# ProPrj_EDA-Piano2_2025-09-29.net
KiCad netlist of a schematic drawn in EasyEDA Pro
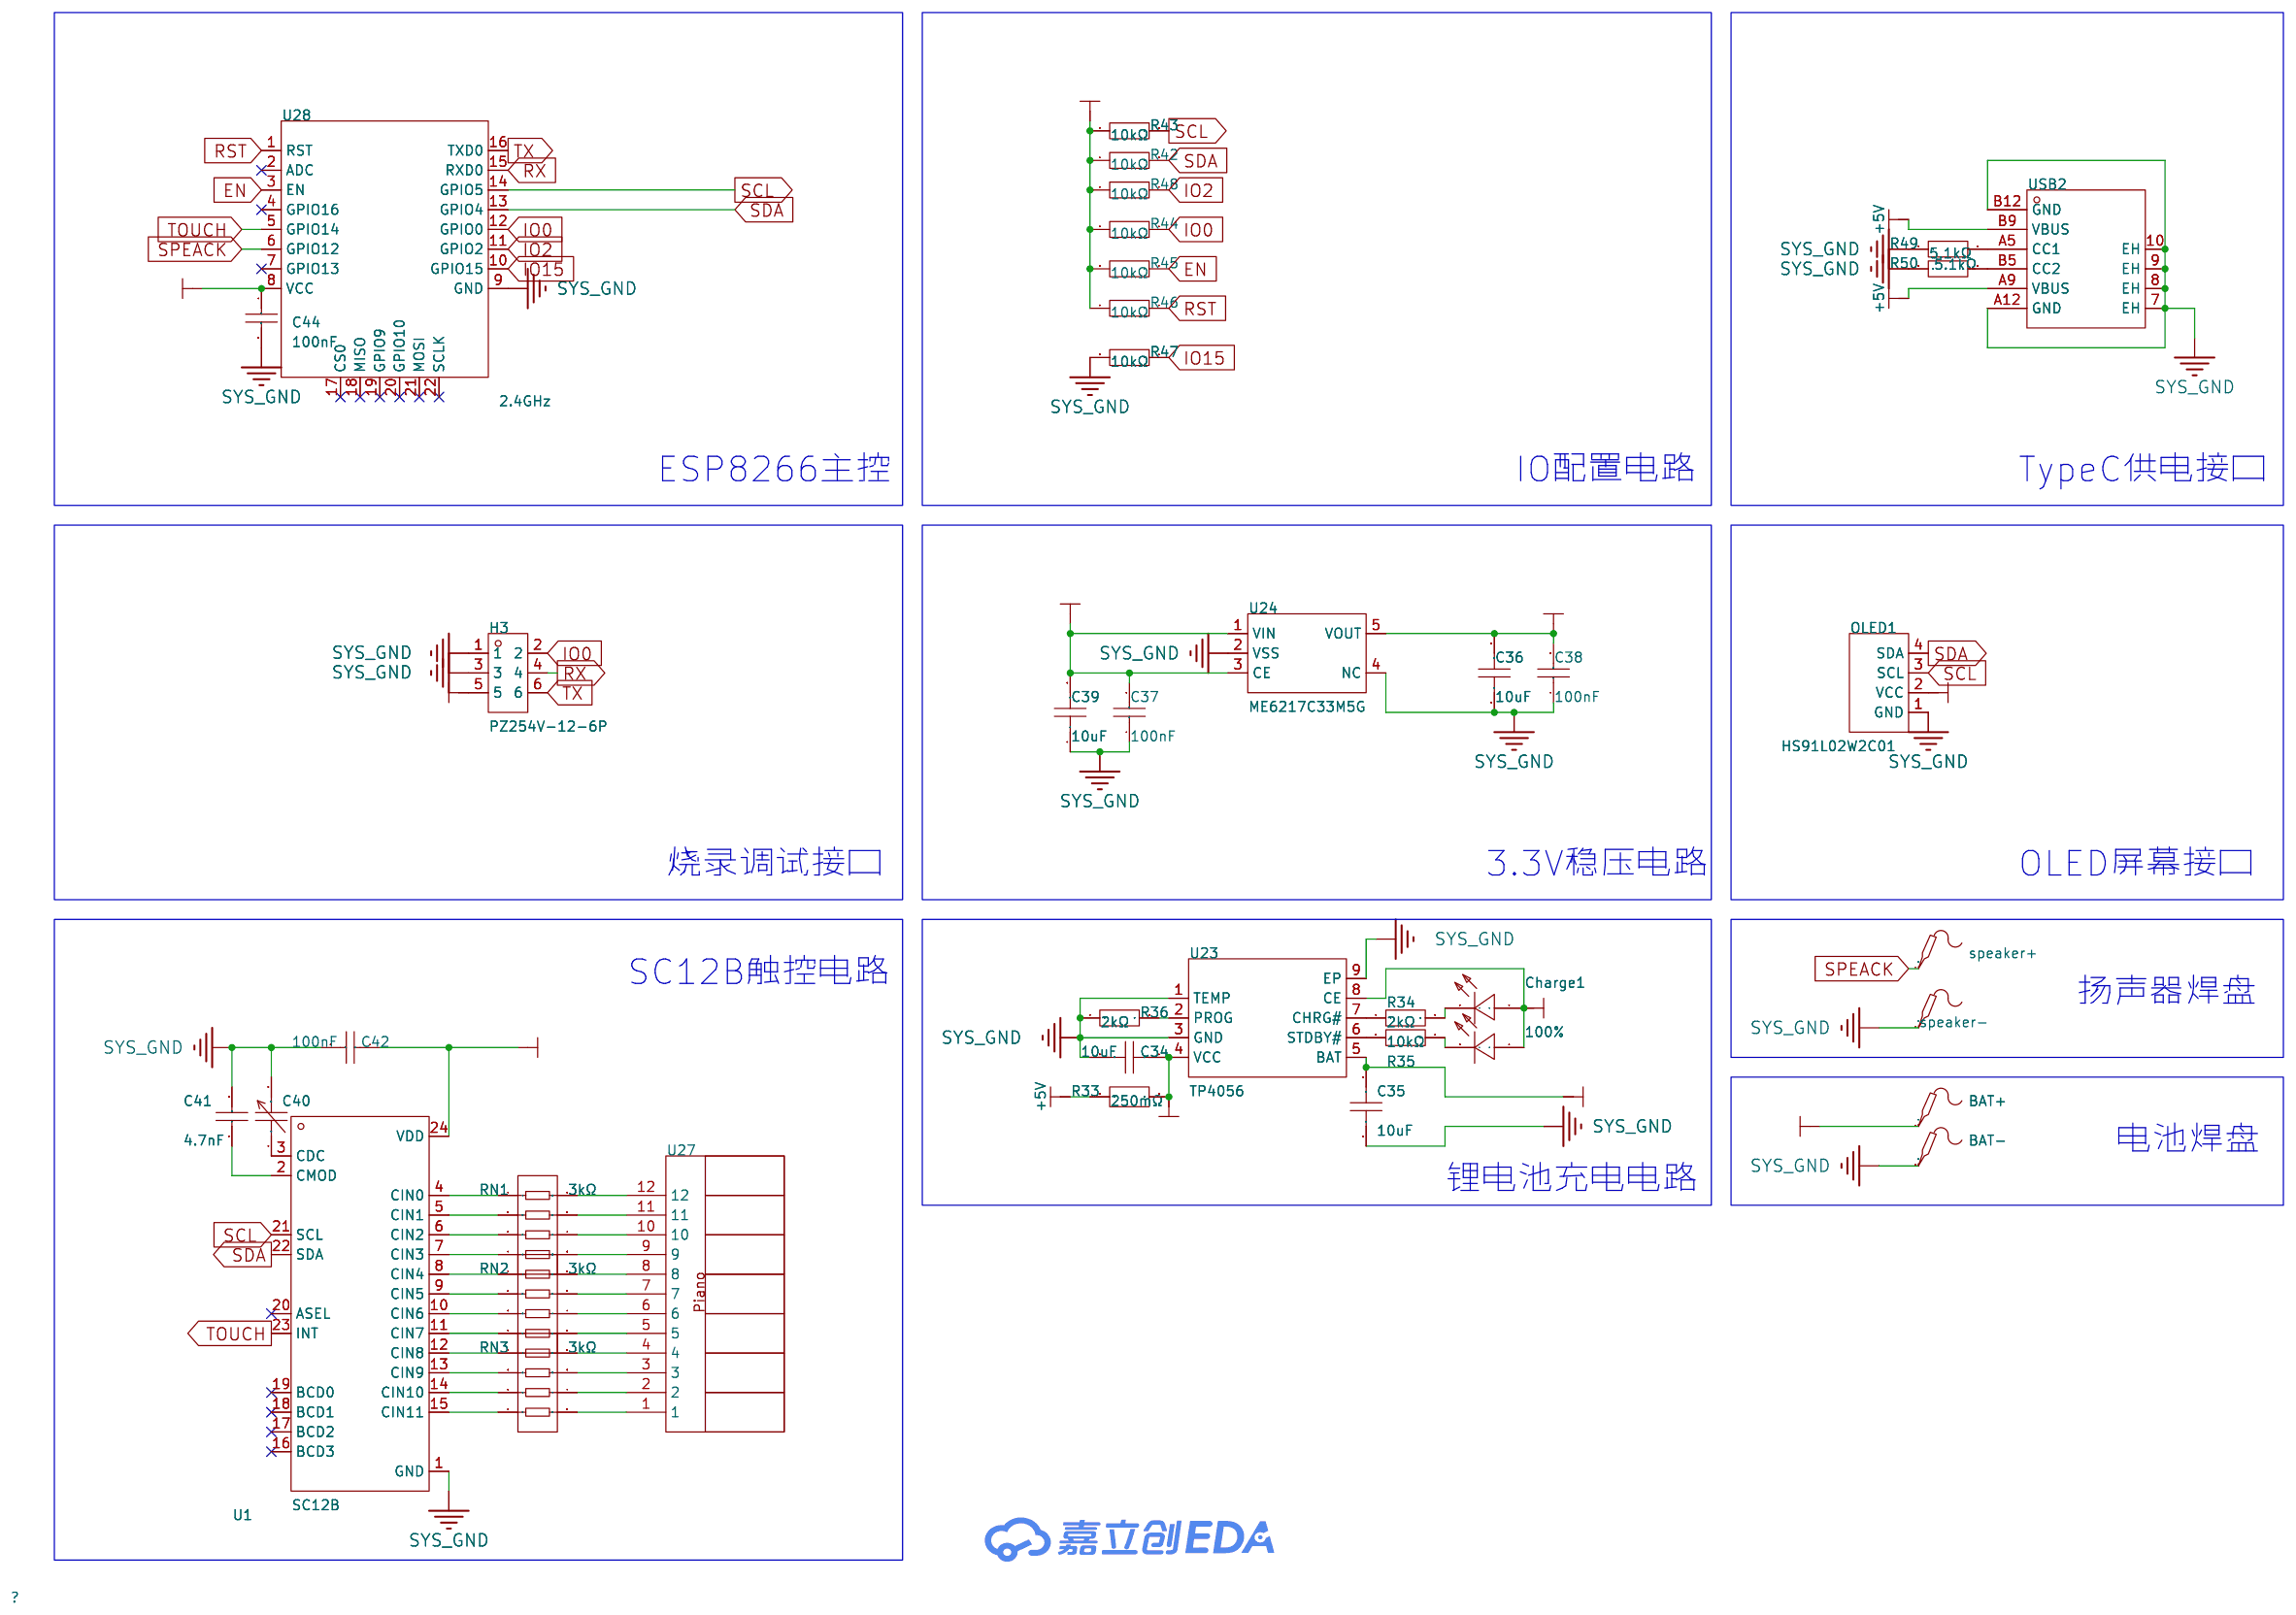
[diagram p0: schematic sheet]

(export (version "E")
  (design (tool "Eeschema 10.0.6"))
  (components
    (comp (ref "100%")
      (value "NCD0805R1")
      (footprint "easyedapro:LED0805-R-RD")
      (fields (field (name "Manufacturer") "国星光电"))
      (libsource (lib "easyedapro") (part "FC-2012HRK-620D"))
    )
    (comp (ref "BAT+")
      (value "~")
      (footprint "easyedapro:Test-Point-0.5mm")
      (description "Test Point 测试点")
      (libsource (lib "easyedapro") (part "Test-Point"))
    )
    (comp (ref "BAT-")
      (value "~")
      (footprint "easyedapro:Test-Point-0.5mm")
      (description "Test Point 测试点")
      (libsource (lib "easyedapro") (part "Test-Point"))
    )
    (comp (ref "C34")
      (value "10uF")
      (fields
        (field (name "Manufacturer Part") "CGA0805X5R106K250MT")
        (field (name "Manufacturer") "HRE(芯声)")
      )
      (libsource (lib "easyedapro") (part "CL10A106MA8NRNC"))
    )
    (comp (ref "C35")
      (value "10uF")
      (fields
        (field (name "Manufacturer Part") "CGA0805X5R106K250MT")
        (field (name "Manufacturer") "HRE(芯声)")
      )
      (libsource (lib "easyedapro") (part "CL10A106MA8NRNC"))
    )
    (comp (ref "C36")
      (value "10uF")
      (footprint "easyedapro:C0805")
      (description "容值:10uF;精度:±10%;额定电压:25V;材质(温度系数):X5R;")
      (fields
        (field (name "Manufacturer Part") "CL21A106KAYNNNE")
        (field (name "Manufacturer") "SAMSUNG(三星)")
      )
      (libsource (lib "easyedapro") (part "CL21A106KAYNNNE"))
    )
    (comp (ref "C37")
      (value "100nF")
      (fields
        (field (name "Manufacturer Part") "FCC0805B104K500DT")
        (field (name "Manufacturer") "FOJAN(富捷)")
      )
      (libsource (lib "easyedapro") (part "CL21A475KAQNNNE"))
    )
    (comp (ref "C38")
      (value "100nF")
      (fields
        (field (name "Manufacturer Part") "FCC0805B104K500DT")
        (field (name "Manufacturer") "FOJAN(富捷)")
      )
      (libsource (lib "easyedapro") (part "CL21A475KAQNNNE"))
    )
    (comp (ref "C39")
      (value "10uF")
      (footprint "easyedapro:C0805")
      (description "容值:10uF;精度:±10%;额定电压:25V;材质(温度系数):X5R;")
      (fields
        (field (name "Manufacturer Part") "CL21A106KAYNNNE")
        (field (name "Manufacturer") "SAMSUNG(三星)")
      )
      (libsource (lib "easyedapro") (part "CL21A106KAYNNNE"))
    )
    (comp (ref "C40")
      (value "STC3ME30-T1")
      (footprint "easyedapro:CAP-SMD_L4.5-W3.2_SGC3S200NM")
      (description "静电容量:8pF~28.5pF;静电容量公差:0%~+50%;额定电压(Vdc):100V;Q值:250@1MHz;")
      (fields (field (name "Manufacturer") "SEHWA(韩国世华)"))
      (libsource (lib "easyedapro") (part "STC3ME30-T1_C22468123"))
    )
    (comp (ref "C41")
      (value "4.7nF")
      (footprint "easyedapro:C0805")
      (description "容值:4.7nF;精度:±10%;额定电压:50V;温度系数:X7R;")
      (fields (field (name "Manufacturer Part") "0805B472K500NT") (field (name "Manufacturer") "FH(风华)"))
      (libsource (lib "easyedapro") (part "0805B472K500NT"))
    )
    (comp (ref "C42")
      (value "100nF")
      (fields
        (field (name "Manufacturer Part") "FCC0805B104K500DT")
        (field (name "Manufacturer") "FOJAN(富捷)")
      )
      (libsource (lib "easyedapro") (part "CL21A475KAQNNNE"))
    )
    (comp (ref "C44")
      (value "100nF")
      (fields
        (field (name "Manufacturer Part") "FCC0805B104K500DT")
        (field (name "Manufacturer") "FOJAN(富捷)")
      )
      (libsource (lib "easyedapro") (part "CL21A475KAQNNNE"))
    )
    (comp (ref "Charge1")
      (value "NCD0805R1")
      (footprint "easyedapro:LED0805-R-RD")
      (fields (field (name "Manufacturer") "国星光电"))
      (libsource (lib "easyedapro") (part "FC-2012HRK-620D"))
    )
    (comp (ref "H3")
      (value "PZ254V-12-6P")
      (footprint "easyedapro:HDR-TH_6P-P2.54-V-M-R2-C3-S2.54")
      (fields (field (name "Manufacturer") "XFCN(兴飞)"))
      (libsource (lib "easyedapro") (part "PZ254V-12-6P"))
    )
    (comp (ref "OLED1")
      (value "HS91L02W2C01")
      (footprint "easyedapro:OLED-TH_L38.0-W12.0_HS91L02W2C01")
      (description "主控芯片:SSD1306;接口类型:I2C;尺寸(inch):0.91;像素分辨率:128x32;")
      (fields (field (name "Manufacturer") "HS(汉昇)"))
      (libsource (lib "easyedapro") (part "HS91L02W2C01"))
    )
    (comp (ref "R33")
      (value "250mΩ")
      (footprint "easyedapro:R0805")
      (description "电阻类型:厚膜电阻;阻值:250mΩ;精度:±5%;功率:125mW;最大工作电压:300V;温度系数:±300ppm/°C;")
      (fields (field (name "Manufacturer Part") "FRL0805JR250TS") (field (name "Manufacturer") "FOJAN(富捷)"))
      (libsource (lib "easyedapro") (part "FRL0805JR250TS"))
    )
    (comp (ref "R34")
      (value "2kΩ")
      (footprint "easyedapro:R0805")
      (description "电阻类型:厚膜电阻;阻值:2kΩ;精度:±1%;功率:125mW;最大工作电压:150V;温度系数:±100ppm/°C;")
      (fields
        (field (name "Manufacturer Part") "0805W8F2001T5E")
        (field (name "Manufacturer") "UNI-ROYAL(厚声)")
      )
      (libsource (lib "easyedapro") (part "0805W8F2001T5E"))
    )
    (comp (ref "R35")
      (value "10kΩ")
      (footprint "easyedapro:R0805")
      (description "电阻类型:厚膜电阻;阻值:10kΩ;精度:±1%;功率:125mW;最大工作电压:150V;温度系数:±100ppm/°C;")
      (fields
        (field (name "Manufacturer Part") "0805W8F1002T5E")
        (field (name "Manufacturer") "UNI-ROYAL(厚声)")
      )
      (libsource (lib "easyedapro") (part "0805W8F1002T5E"))
    )
    (comp (ref "R36")
      (value "2kΩ")
      (footprint "easyedapro:R0805")
      (description "电阻类型:厚膜电阻;阻值:2kΩ;精度:±1%;功率:125mW;最大工作电压:150V;温度系数:±100ppm/°C;")
      (fields
        (field (name "Manufacturer Part") "0805W8F2001T5E")
        (field (name "Manufacturer") "UNI-ROYAL(厚声)")
      )
      (libsource (lib "easyedapro") (part "0805W8F2001T5E"))
    )
    (comp (ref "R42")
      (value "10kΩ")
      (footprint "easyedapro:R0805")
      (description "电阻类型:厚膜电阻;阻值:10kΩ;精度:±1%;功率:125mW;最大工作电压:150V;温度系数:±100ppm/°C;")
      (fields
        (field (name "Manufacturer Part") "0805W8F1002T5E")
        (field (name "Manufacturer") "UNI-ROYAL(厚声)")
      )
      (libsource (lib "easyedapro") (part "0805W8F1002T5E"))
    )
    (comp (ref "R43")
      (value "10kΩ")
      (footprint "easyedapro:R0805")
      (description "电阻类型:厚膜电阻;阻值:10kΩ;精度:±1%;功率:125mW;最大工作电压:150V;温度系数:±100ppm/°C;")
      (fields
        (field (name "Manufacturer Part") "0805W8F1002T5E")
        (field (name "Manufacturer") "UNI-ROYAL(厚声)")
      )
      (libsource (lib "easyedapro") (part "0805W8F1002T5E"))
    )
    (comp (ref "R44")
      (value "10kΩ")
      (footprint "easyedapro:R0805")
      (description "电阻类型:厚膜电阻;阻值:10kΩ;精度:±1%;功率:125mW;最大工作电压:150V;温度系数:±100ppm/°C;")
      (fields
        (field (name "Manufacturer Part") "0805W8F1002T5E")
        (field (name "Manufacturer") "UNI-ROYAL(厚声)")
      )
      (libsource (lib "easyedapro") (part "0805W8F1002T5E"))
    )
    (comp (ref "R45")
      (value "10kΩ")
      (footprint "easyedapro:R0805")
      (description "电阻类型:厚膜电阻;阻值:10kΩ;精度:±1%;功率:125mW;最大工作电压:150V;温度系数:±100ppm/°C;")
      (fields
        (field (name "Manufacturer Part") "0805W8F1002T5E")
        (field (name "Manufacturer") "UNI-ROYAL(厚声)")
      )
      (libsource (lib "easyedapro") (part "0805W8F1002T5E"))
    )
    (comp (ref "R46")
      (value "10kΩ")
      (footprint "easyedapro:R0805")
      (description "电阻类型:厚膜电阻;阻值:10kΩ;精度:±1%;功率:125mW;最大工作电压:150V;温度系数:±100ppm/°C;")
      (fields
        (field (name "Manufacturer Part") "0805W8F1002T5E")
        (field (name "Manufacturer") "UNI-ROYAL(厚声)")
      )
      (libsource (lib "easyedapro") (part "0805W8F1002T5E"))
    )
    (comp (ref "R47")
      (value "10kΩ")
      (footprint "easyedapro:R0805")
      (description "电阻类型:厚膜电阻;阻值:10kΩ;精度:±1%;功率:125mW;最大工作电压:150V;温度系数:±100ppm/°C;")
      (fields
        (field (name "Manufacturer Part") "0805W8F1002T5E")
        (field (name "Manufacturer") "UNI-ROYAL(厚声)")
      )
      (libsource (lib "easyedapro") (part "0805W8F1002T5E"))
    )
    (comp (ref "R48")
      (value "10kΩ")
      (footprint "easyedapro:R0805")
      (description "电阻类型:厚膜电阻;阻值:10kΩ;精度:±1%;功率:125mW;最大工作电压:150V;温度系数:±100ppm/°C;")
      (fields
        (field (name "Manufacturer Part") "0805W8F1002T5E")
        (field (name "Manufacturer") "UNI-ROYAL(厚声)")
      )
      (libsource (lib "easyedapro") (part "0805W8F1002T5E"))
    )
    (comp (ref "R49")
      (value "5.1kΩ")
      (footprint "easyedapro:R0805")
      (description "电阻类型:厚膜电阻;阻值:5.1kΩ;精度:±1%;功率:125mW;工作电压:150V;温度系数:±100ppm/°C;")
      (fields
        (field (name "Manufacturer Part") "0805W8F5101T5E")
        (field (name "Manufacturer") "UNI-ROYAL(厚声)")
      )
      (libsource (lib "easyedapro") (part "0805W8F5101T5E"))
    )
    (comp (ref "R50")
      (value "5.1kΩ")
      (footprint "easyedapro:R0805")
      (description "电阻类型:厚膜电阻;阻值:5.1kΩ;精度:±1%;功率:125mW;工作电压:150V;温度系数:±100ppm/°C;")
      (fields
        (field (name "Manufacturer Part") "0805W8F5101T5E")
        (field (name "Manufacturer") "UNI-ROYAL(厚声)")
      )
      (libsource (lib "easyedapro") (part "0805W8F5101T5E"))
    )
    (comp (ref "RN1")
      (value "3kΩ")
      (footprint "easyedapro:RES-ARRAY-SMD_0603-8P-L3.2-W1.6-BL")
      (description "电阻器数:4;阻值:3kΩ;精度:±1%;单个元件功率:62.5mW;温度系数:±200ppm/°C;")
      (fields
        (field (name "Manufacturer Part") "4D03WGF3001T5E")
        (field (name "Manufacturer") "UNI-ROYAL(厚声)")
      )
      (libsource (lib "easyedapro") (part "4D03WGF3001T5E"))
    )
    (comp (ref "RN2")
      (value "3kΩ")
      (footprint "easyedapro:RES-ARRAY-SMD_0603-8P-L3.2-W1.6-BL")
      (description "电阻器数:4;阻值:3kΩ;精度:±1%;单个元件功率:62.5mW;温度系数:±200ppm/°C;")
      (fields
        (field (name "Manufacturer Part") "4D03WGF3001T5E")
        (field (name "Manufacturer") "UNI-ROYAL(厚声)")
      )
      (libsource (lib "easyedapro") (part "4D03WGF3001T5E"))
    )
    (comp (ref "RN3")
      (value "3kΩ")
      (footprint "easyedapro:RES-ARRAY-SMD_0603-8P-L3.2-W1.6-BL")
      (description "电阻器数:4;阻值:3kΩ;精度:±1%;单个元件功率:62.5mW;温度系数:±200ppm/°C;")
      (fields
        (field (name "Manufacturer Part") "4D03WGF3001T5E")
        (field (name "Manufacturer") "UNI-ROYAL(厚声)")
      )
      (libsource (lib "easyedapro") (part "4D03WGF3001T5E"))
    )
    (comp (ref "speaker+")
      (value "~")
      (footprint "easyedapro:Test-Point-0.5mm")
      (description "Test Point 测试点")
      (libsource (lib "easyedapro") (part "Test-Point"))
    )
    (comp (ref "speaker-")
      (value "~")
      (footprint "easyedapro:Test-Point-0.5mm")
      (description "Test Point 测试点")
      (libsource (lib "easyedapro") (part "Test-Point"))
    )
    (comp (ref "U1")
      (value "SC12B")
      (footprint "easyedapro:SSOP-24_L8.7-W3.9-P0.64-LS6.0-BL")
      (description "通道数:12;芯片功能:电容式触摸;是否自锁:-;")
      (fields (field (name "Manufacturer") "icman(晶尊微)"))
      (libsource (lib "easyedapro") (part "SC12B"))
    )
    (comp (ref "U23")
      (value "TP4056")
      (footprint "easyedapro:ESOP-8_L4.9-W3.9-P1.27-LS6.0-BL-EP")
      (fields (field (name "Manufacturer") "UMW(友台半导体)"))
      (libsource (lib "easyedapro") (part "TP4056_C725790"))
    )
    (comp (ref "U24")
      (value "ME6217C33M5G")
      (footprint "easyedapro:SOT-23-5_L3.0-W1.7-P0.95-LS2.8-BR")
      (description "输出类型:固定;工作电压:6.5V;输出电压:3.3V;输出电流:800mA;电源纹波抑制比(PSRR):65dB@(1kHz);输出极性:正极;")
      (fields (field (name "Manufacturer") "MICRONE(南京微盟)"))
      (libsource (lib "easyedapro") (part "ME6217C33M5G"))
    )
    (comp (ref "U27")
      (value "~")
      (footprint "easyedapro:Piano")
      (libsource (lib "easyedapro") (part "Piano"))
    )
    (comp (ref "U28")
      (value "2.4GHz")
      (footprint "easyedapro:WIFIM-SMD_ESP-12F-ESP8266MOD")
      (description "核心处理器:ESP8266芯片;频率:2.4GHz;天线形式:板载PCB天线;发射功率:16dBm;接收灵敏度:-90dBm;")
      (fields
        (field (name "Manufacturer Part") "ESP-12F(ESP8266MOD)")
        (field (name "Manufacturer") "Ai-Thinker(安信可)")
      )
      (libsource (lib "easyedapro") (part "ESP-12F(ESP8266MOD)"))
    )
    (comp (ref "USB2")
      (value "U262-061N-4BVC11")
      (footprint "easyedapro:USB-SMD_U262-061N-4BVC11")
      (fields (field (name "Manufacturer") "XKB Connection(中国星坤)"))
      (libsource (lib "easyedapro") (part "U262-061N-4BVC11"))
    )
  )
  (nets
    (net (code "1") (name "+5V") (class "Default")
      (node (ref "R33") (pin "1") (pinfunction "1_1") (pintype "unspecified"))
      (node (ref "USB2") (pin "A9") (pinfunction "VBUS_A9") (pintype "unspecified"))
      (node (ref "USB2") (pin "B9") (pinfunction "VBUS_B9") (pintype "unspecified"))
    )
    (net (code "2") (name "BAT") (class "Default")
      (node (ref "BAT+") (pin "1") (pinfunction "1_1") (pintype "input"))
      (node (ref "C35") (pin "1") (pinfunction "1_1") (pintype "unspecified"))
      (node (ref "C37") (pin "2") (pinfunction "2_2") (pintype "input"))
      (node (ref "C39") (pin "2") (pinfunction "2_2") (pintype "unspecified"))
      (node (ref "U23") (pin "5") (pinfunction "BAT_5") (pintype "unspecified"))
      (node (ref "U24") (pin "1") (pinfunction "VIN_1") (pintype "unspecified"))
      (node (ref "U24") (pin "3") (pinfunction "CE_3") (pintype "unspecified"))
    )
    (net (code "3") (name "EN") (class "Default")
      (node (ref "R45") (pin "1") (pinfunction "1_1") (pintype "input"))
      (node (ref "U28") (pin "3") (pinfunction "EN_3") (pintype "unspecified"))
    )
    (net (code "4") (name "IO0") (class "Default")
      (node (ref "H3") (pin "2") (pinfunction "2_2") (pintype "unspecified"))
      (node (ref "R44") (pin "1") (pinfunction "1_1") (pintype "input"))
      (node (ref "U28") (pin "12") (pinfunction "GPIO0_12") (pintype "unspecified"))
    )
    (net (code "5") (name "IO2") (class "Default")
      (node (ref "R48") (pin "1") (pinfunction "1_1") (pintype "input"))
      (node (ref "U28") (pin "11") (pinfunction "GPIO2_11") (pintype "unspecified"))
    )
    (net (code "6") (name "IO15") (class "Default")
      (node (ref "R47") (pin "1") (pinfunction "1_1") (pintype "input"))
      (node (ref "U28") (pin "10") (pinfunction "GPIO15_10") (pintype "unspecified"))
    )
    (net (code "7") (name "Net-(100%--)") (class "Default")
      (node (ref "100%") (pin "2") (pinfunction "-_2") (pintype "unspecified"))
      (node (ref "R35") (pin "1") (pinfunction "1_1") (pintype "input"))
    )
    (net (code "8") (name "Net-(Charge1--)") (class "Default")
      (node (ref "Charge1") (pin "2") (pinfunction "-_2") (pintype "unspecified"))
      (node (ref "R34") (pin "2") (pinfunction "2_2") (pintype "input"))
    )
    (net (code "9") (name "Net-(RN1-Pad5)") (class "Default")
      (node (ref "RN1") (pin "5") (pinfunction "5_5") (pintype "unspecified"))
      (node (ref "U27") (pin "12") (pinfunction "12_12") (pintype "input"))
    )
    (net (code "10") (name "Net-(RN1-Pad6)") (class "Default")
      (node (ref "RN1") (pin "6") (pinfunction "6_6") (pintype "unspecified"))
      (node (ref "U27") (pin "11") (pinfunction "11_11") (pintype "input"))
    )
    (net (code "11") (name "Net-(RN1-Pad7)") (class "Default")
      (node (ref "RN1") (pin "7") (pinfunction "7_7") (pintype "unspecified"))
      (node (ref "U27") (pin "10") (pinfunction "10_10") (pintype "input"))
    )
    (net (code "12") (name "Net-(RN1-Pad8)") (class "Default")
      (node (ref "RN1") (pin "8") (pinfunction "8_8") (pintype "unspecified"))
      (node (ref "U27") (pin "9") (pinfunction "9_9") (pintype "input"))
    )
    (net (code "13") (name "Net-(RN2-Pad5)") (class "Default")
      (node (ref "RN2") (pin "5") (pinfunction "5_5") (pintype "unspecified"))
      (node (ref "U27") (pin "8") (pinfunction "8_8") (pintype "input"))
    )
    (net (code "14") (name "Net-(RN2-Pad6)") (class "Default")
      (node (ref "RN2") (pin "6") (pinfunction "6_6") (pintype "unspecified"))
      (node (ref "U27") (pin "7") (pinfunction "7_7") (pintype "input"))
    )
    (net (code "15") (name "Net-(RN2-Pad7)") (class "Default")
      (node (ref "RN2") (pin "7") (pinfunction "7_7") (pintype "unspecified"))
      (node (ref "U27") (pin "6") (pinfunction "6_6") (pintype "input"))
    )
    (net (code "16") (name "Net-(RN2-Pad8)") (class "Default")
      (node (ref "RN2") (pin "8") (pinfunction "8_8") (pintype "unspecified"))
      (node (ref "U27") (pin "5") (pinfunction "5_5") (pintype "input"))
    )
    (net (code "17") (name "Net-(RN3-Pad5)") (class "Default")
      (node (ref "RN3") (pin "5") (pinfunction "5_5") (pintype "unspecified"))
      (node (ref "U27") (pin "4") (pinfunction "4_4") (pintype "input"))
    )
    (net (code "18") (name "Net-(RN3-Pad6)") (class "Default")
      (node (ref "RN3") (pin "6") (pinfunction "6_6") (pintype "unspecified"))
      (node (ref "U27") (pin "3") (pinfunction "3_3") (pintype "input"))
    )
    (net (code "19") (name "Net-(RN3-Pad7)") (class "Default")
      (node (ref "RN3") (pin "7") (pinfunction "7_7") (pintype "unspecified"))
      (node (ref "U27") (pin "2") (pinfunction "2_2") (pintype "input"))
    )
    (net (code "20") (name "Net-(RN3-Pad8)") (class "Default")
      (node (ref "RN3") (pin "8") (pinfunction "8_8") (pintype "unspecified"))
      (node (ref "U27") (pin "1") (pinfunction "1_1") (pintype "input"))
    )
    (net (code "21") (name "Net-(U1-CDC)") (class "Default")
      (node (ref "C40") (pin "1") (pinfunction "1_1") (pintype "unspecified"))
      (node (ref "U1") (pin "3") (pinfunction "CDC_3") (pintype "unspecified"))
    )
    (net (code "22") (name "Net-(U1-CIN0)") (class "Default")
      (node (ref "RN1") (pin "4") (pinfunction "4_4") (pintype "unspecified"))
      (node (ref "U1") (pin "4") (pinfunction "CIN0_4") (pintype "unspecified"))
    )
    (net (code "23") (name "Net-(U1-CIN1)") (class "Default")
      (node (ref "RN1") (pin "3") (pinfunction "3_3") (pintype "unspecified"))
      (node (ref "U1") (pin "5") (pinfunction "CIN1_5") (pintype "unspecified"))
    )
    (net (code "24") (name "Net-(U1-CIN2)") (class "Default")
      (node (ref "RN1") (pin "2") (pinfunction "2_2") (pintype "unspecified"))
      (node (ref "U1") (pin "6") (pinfunction "CIN2_6") (pintype "unspecified"))
    )
    (net (code "25") (name "Net-(U1-CIN3)") (class "Default")
      (node (ref "RN1") (pin "1") (pinfunction "1_1") (pintype "unspecified"))
      (node (ref "U1") (pin "7") (pinfunction "CIN3_7") (pintype "unspecified"))
    )
    (net (code "26") (name "Net-(U1-CIN4)") (class "Default")
      (node (ref "RN2") (pin "4") (pinfunction "4_4") (pintype "unspecified"))
      (node (ref "U1") (pin "8") (pinfunction "CIN4_8") (pintype "unspecified"))
    )
    (net (code "27") (name "Net-(U1-CIN5)") (class "Default")
      (node (ref "RN2") (pin "3") (pinfunction "3_3") (pintype "unspecified"))
      (node (ref "U1") (pin "9") (pinfunction "CIN5_9") (pintype "unspecified"))
    )
    (net (code "28") (name "Net-(U1-CIN6)") (class "Default")
      (node (ref "RN2") (pin "2") (pinfunction "2_2") (pintype "unspecified"))
      (node (ref "U1") (pin "10") (pinfunction "CIN6_10") (pintype "unspecified"))
    )
    (net (code "29") (name "Net-(U1-CIN7)") (class "Default")
      (node (ref "RN2") (pin "1") (pinfunction "1_1") (pintype "unspecified"))
      (node (ref "U1") (pin "11") (pinfunction "CIN7_11") (pintype "unspecified"))
    )
    (net (code "30") (name "Net-(U1-CIN8)") (class "Default")
      (node (ref "RN3") (pin "4") (pinfunction "4_4") (pintype "unspecified"))
      (node (ref "U1") (pin "12") (pinfunction "CIN8_12") (pintype "unspecified"))
    )
    (net (code "31") (name "Net-(U1-CIN9)") (class "Default")
      (node (ref "RN3") (pin "3") (pinfunction "3_3") (pintype "unspecified"))
      (node (ref "U1") (pin "13") (pinfunction "CIN9_13") (pintype "unspecified"))
    )
    (net (code "32") (name "Net-(U1-CIN10)") (class "Default")
      (node (ref "RN3") (pin "2") (pinfunction "2_2") (pintype "unspecified"))
      (node (ref "U1") (pin "14") (pinfunction "CIN10_14") (pintype "unspecified"))
    )
    (net (code "33") (name "Net-(U1-CIN11)") (class "Default")
      (node (ref "RN3") (pin "1") (pinfunction "1_1") (pintype "unspecified"))
      (node (ref "U1") (pin "15") (pinfunction "CIN11_15") (pintype "unspecified"))
    )
    (net (code "34") (name "Net-(U1-CMOD)") (class "Default")
      (node (ref "C41") (pin "1") (pinfunction "1_1") (pintype "input"))
      (node (ref "U1") (pin "2") (pinfunction "CMOD_2") (pintype "unspecified"))
    )
    (net (code "35") (name "Net-(U23-CHRG#)") (class "Default")
      (node (ref "R34") (pin "1") (pinfunction "1_1") (pintype "input"))
      (node (ref "U23") (pin "7") (pinfunction "CHRG#_7") (pintype "unspecified"))
    )
    (net (code "36") (name "Net-(U23-PROG)") (class "Default")
      (node (ref "R36") (pin "2") (pinfunction "2_2") (pintype "input"))
      (node (ref "U23") (pin "2") (pinfunction "PROG_2") (pintype "unspecified"))
    )
    (net (code "37") (name "Net-(U23-STDBY#)") (class "Default")
      (node (ref "R35") (pin "2") (pinfunction "2_2") (pintype "input"))
      (node (ref "U23") (pin "6") (pinfunction "STDBY#_6") (pintype "unspecified"))
    )
    (net (code "38") (name "Net-(USB2-CC1)") (class "Default")
      (node (ref "R49") (pin "2") (pinfunction "2_2") (pintype "input"))
      (node (ref "USB2") (pin "A5") (pinfunction "CC1_A5") (pintype "unspecified"))
    )
    (net (code "39") (name "Net-(USB2-CC2)") (class "Default")
      (node (ref "R50") (pin "2") (pinfunction "2_2") (pintype "input"))
      (node (ref "USB2") (pin "B5") (pinfunction "CC2_B5") (pintype "unspecified"))
    )
    (net (code "40") (name "RST") (class "Default")
      (node (ref "R46") (pin "1") (pinfunction "1_1") (pintype "input"))
      (node (ref "U28") (pin "1") (pinfunction "RST_1") (pintype "unspecified"))
    )
    (net (code "41") (name "RX") (class "Default")
      (node (ref "H3") (pin "4") (pinfunction "4_4") (pintype "unspecified"))
      (node (ref "U28") (pin "15") (pinfunction "RXD0_15") (pintype "unspecified"))
    )
    (net (code "42") (name "SCL") (class "Default")
      (node (ref "OLED1") (pin "3") (pinfunction "SCL_3") (pintype "unspecified"))
      (node (ref "R43") (pin "2") (pinfunction "2_2") (pintype "input"))
      (node (ref "U1") (pin "21") (pinfunction "SCL_21") (pintype "unspecified"))
      (node (ref "U28") (pin "14") (pinfunction "GPIO5_14") (pintype "unspecified"))
    )
    (net (code "43") (name "SDA") (class "Default")
      (node (ref "OLED1") (pin "4") (pinfunction "SDA_4") (pintype "unspecified"))
      (node (ref "R42") (pin "2") (pinfunction "2_2") (pintype "input"))
      (node (ref "U1") (pin "22") (pinfunction "SDA_22") (pintype "unspecified"))
      (node (ref "U28") (pin "13") (pinfunction "GPIO4_13") (pintype "unspecified"))
    )
    (net (code "44") (name "SPEACK") (class "Default")
      (node (ref "U28") (pin "6") (pinfunction "GPIO12_6") (pintype "unspecified"))
      (node (ref "speaker+") (pin "1") (pinfunction "1_1") (pintype "input"))
    )
    (net (code "45") (name "SYSTEM_3V3") (class "Default")
      (node (ref "C36") (pin "2") (pinfunction "2_2") (pintype "unspecified"))
      (node (ref "C38") (pin "2") (pinfunction "2_2") (pintype "input"))
      (node (ref "C42") (pin "1") (pinfunction "1_1") (pintype "input"))
      (node (ref "C44") (pin "1") (pinfunction "1_1") (pintype "input"))
      (node (ref "H3") (pin "5") (pinfunction "5_5") (pintype "unspecified"))
      (node (ref "OLED1") (pin "2") (pinfunction "VCC_2") (pintype "unspecified"))
      (node (ref "R42") (pin "1") (pinfunction "1_1") (pintype "input"))
      (node (ref "R43") (pin "1") (pinfunction "1_1") (pintype "input"))
      (node (ref "R44") (pin "2") (pinfunction "2_2") (pintype "input"))
      (node (ref "R45") (pin "2") (pinfunction "2_2") (pintype "input"))
      (node (ref "R46") (pin "2") (pinfunction "2_2") (pintype "input"))
      (node (ref "R48") (pin "2") (pinfunction "2_2") (pintype "input"))
      (node (ref "U1") (pin "24") (pinfunction "VDD_24") (pintype "unspecified"))
      (node (ref "U24") (pin "5") (pinfunction "VOUT_5") (pintype "unspecified"))
      (node (ref "U28") (pin "8") (pinfunction "VCC_8") (pintype "unspecified"))
    )
    (net (code "46") (name "SYS_GND") (class "Default")
      (node (ref "BAT-") (pin "1") (pinfunction "1_1") (pintype "input"))
      (node (ref "C34") (pin "2") (pinfunction "2_2") (pintype "unspecified"))
      (node (ref "C35") (pin "2") (pinfunction "2_2") (pintype "unspecified"))
      (node (ref "C36") (pin "1") (pinfunction "1_1") (pintype "unspecified"))
      (node (ref "C37") (pin "1") (pinfunction "1_1") (pintype "input"))
      (node (ref "C38") (pin "1") (pinfunction "1_1") (pintype "input"))
      (node (ref "C39") (pin "1") (pinfunction "1_1") (pintype "unspecified"))
      (node (ref "C40") (pin "2") (pinfunction "2_2") (pintype "unspecified"))
      (node (ref "C41") (pin "2") (pinfunction "2_2") (pintype "input"))
      (node (ref "C42") (pin "2") (pinfunction "2_2") (pintype "input"))
      (node (ref "C44") (pin "2") (pinfunction "2_2") (pintype "input"))
      (node (ref "H3") (pin "1") (pinfunction "1_1") (pintype "unspecified"))
      (node (ref "H3") (pin "3") (pinfunction "3_3") (pintype "unspecified"))
      (node (ref "OLED1") (pin "1") (pinfunction "GND_1") (pintype "unspecified"))
      (node (ref "R36") (pin "1") (pinfunction "1_1") (pintype "input"))
      (node (ref "R47") (pin "2") (pinfunction "2_2") (pintype "input"))
      (node (ref "R49") (pin "1") (pinfunction "1_1") (pintype "input"))
      (node (ref "R50") (pin "1") (pinfunction "1_1") (pintype "input"))
      (node (ref "U1") (pin "1") (pinfunction "GND_1") (pintype "unspecified"))
      (node (ref "U23") (pin "1") (pinfunction "TEMP_1") (pintype "unspecified"))
      (node (ref "U23") (pin "3") (pinfunction "GND_3") (pintype "unspecified"))
      (node (ref "U23") (pin "9") (pinfunction "EP_9") (pintype "unspecified"))
      (node (ref "U24") (pin "2") (pinfunction "VSS_2") (pintype "unspecified"))
      (node (ref "U24") (pin "4") (pinfunction "NC_4") (pintype "unspecified"))
      (node (ref "U28") (pin "9") (pinfunction "GND_9") (pintype "unspecified"))
      (node (ref "USB2") (pin "10") (pinfunction "EH_10") (pintype "unspecified"))
      (node (ref "USB2") (pin "7") (pinfunction "EH_7") (pintype "unspecified"))
      (node (ref "USB2") (pin "8") (pinfunction "EH_8") (pintype "unspecified"))
      (node (ref "USB2") (pin "9") (pinfunction "EH_9") (pintype "unspecified"))
      (node (ref "USB2") (pin "A12") (pinfunction "GND_A12") (pintype "unspecified"))
      (node (ref "USB2") (pin "B12") (pinfunction "GND_B12") (pintype "unspecified"))
      (node (ref "speaker-") (pin "1") (pinfunction "1_1") (pintype "input"))
    )
    (net (code "47") (name "TOUCH") (class "Default")
      (node (ref "U1") (pin "23") (pinfunction "INT_23") (pintype "unspecified"))
      (node (ref "U28") (pin "5") (pinfunction "GPIO14_5") (pintype "unspecified"))
    )
    (net (code "48") (name "TP4056_VCC") (class "Default")
      (node (ref "100%") (pin "1") (pinfunction "+_1") (pintype "unspecified"))
      (node (ref "C34") (pin "1") (pinfunction "1_1") (pintype "unspecified"))
      (node (ref "Charge1") (pin "1") (pinfunction "+_1") (pintype "unspecified"))
      (node (ref "R33") (pin "2") (pinfunction "2_2") (pintype "unspecified"))
      (node (ref "U23") (pin "4") (pinfunction "VCC_4") (pintype "unspecified"))
      (node (ref "U23") (pin "8") (pinfunction "CE_8") (pintype "unspecified"))
    )
    (net (code "49") (name "TX") (class "Default")
      (node (ref "H3") (pin "6") (pinfunction "6_6") (pintype "unspecified"))
      (node (ref "U28") (pin "16") (pinfunction "TXD0_16") (pintype "unspecified"))
    )
    (net (code "50") (name "unconnected-(U1-ASEL-Pad20)") (class "Default")
      (node (ref "U1") (pin "20") (pinfunction "ASEL_20") (pintype "unspecified+no_connect"))
    )
    (net (code "51") (name "unconnected-(U1-BCD0-Pad19)") (class "Default")
      (node (ref "U1") (pin "19") (pinfunction "BCD0_19") (pintype "unspecified+no_connect"))
    )
    (net (code "52") (name "unconnected-(U1-BCD1-Pad18)") (class "Default")
      (node (ref "U1") (pin "18") (pinfunction "BCD1_18") (pintype "unspecified+no_connect"))
    )
    (net (code "53") (name "unconnected-(U1-BCD2-Pad17)") (class "Default")
      (node (ref "U1") (pin "17") (pinfunction "BCD2_17") (pintype "unspecified+no_connect"))
    )
    (net (code "54") (name "unconnected-(U1-BCD3-Pad16)") (class "Default")
      (node (ref "U1") (pin "16") (pinfunction "BCD3_16") (pintype "unspecified+no_connect"))
    )
    (net (code "55") (name "unconnected-(U28-ADC-Pad2)") (class "Default")
      (node (ref "U28") (pin "2") (pinfunction "ADC_2") (pintype "unspecified+no_connect"))
    )
    (net (code "56") (name "unconnected-(U28-CS0-Pad17)") (class "Default")
      (node (ref "U28") (pin "17") (pinfunction "CS0_17") (pintype "unspecified+no_connect"))
    )
    (net (code "57") (name "unconnected-(U28-GPIO9-Pad19)") (class "Default")
      (node (ref "U28") (pin "19") (pinfunction "GPIO9_19") (pintype "unspecified+no_connect"))
    )
    (net (code "58") (name "unconnected-(U28-GPIO10-Pad20)") (class "Default")
      (node (ref "U28") (pin "20") (pinfunction "GPIO10_20") (pintype "unspecified+no_connect"))
    )
    (net (code "59") (name "unconnected-(U28-GPIO13-Pad7)") (class "Default")
      (node (ref "U28") (pin "7") (pinfunction "GPIO13_7") (pintype "unspecified+no_connect"))
    )
    (net (code "60") (name "unconnected-(U28-GPIO16-Pad4)") (class "Default")
      (node (ref "U28") (pin "4") (pinfunction "GPIO16_4") (pintype "unspecified+no_connect"))
    )
    (net (code "61") (name "unconnected-(U28-MISO-Pad18)") (class "Default")
      (node (ref "U28") (pin "18") (pinfunction "MISO_18") (pintype "unspecified+no_connect"))
    )
    (net (code "62") (name "unconnected-(U28-MOSI-Pad21)") (class "Default")
      (node (ref "U28") (pin "21") (pinfunction "MOSI_21") (pintype "unspecified+no_connect"))
    )
    (net (code "63") (name "unconnected-(U28-SCLK-Pad22)") (class "Default")
      (node (ref "U28") (pin "22") (pinfunction "SCLK_22") (pintype "unspecified+no_connect"))
    )
  )
)
